# PRO_controller.net
KiCad netlist of a schematic drawn in EAGLE
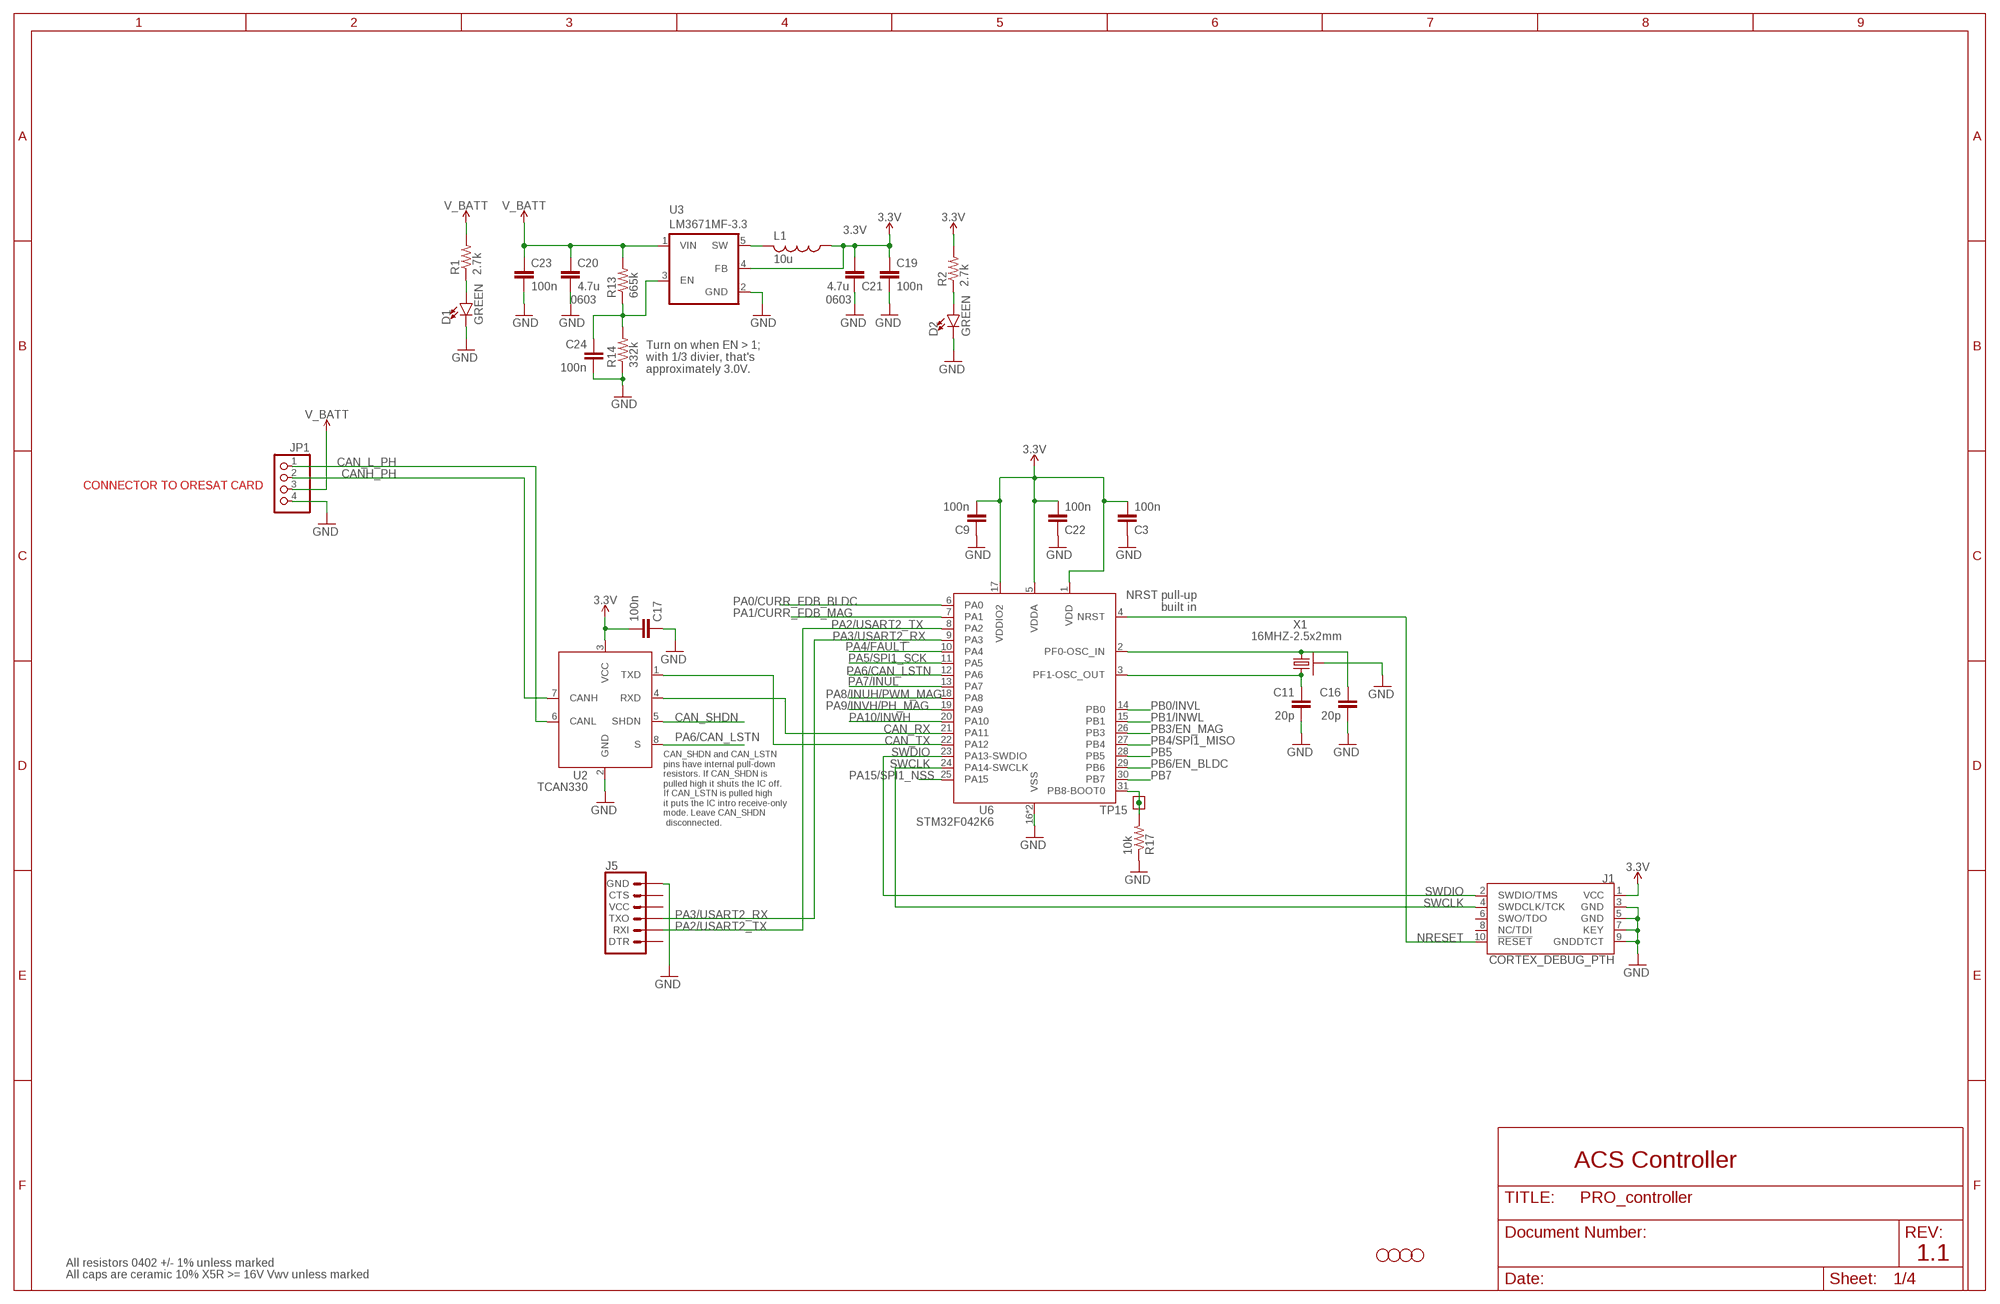
[diagram p0: schematic, sheet 1]
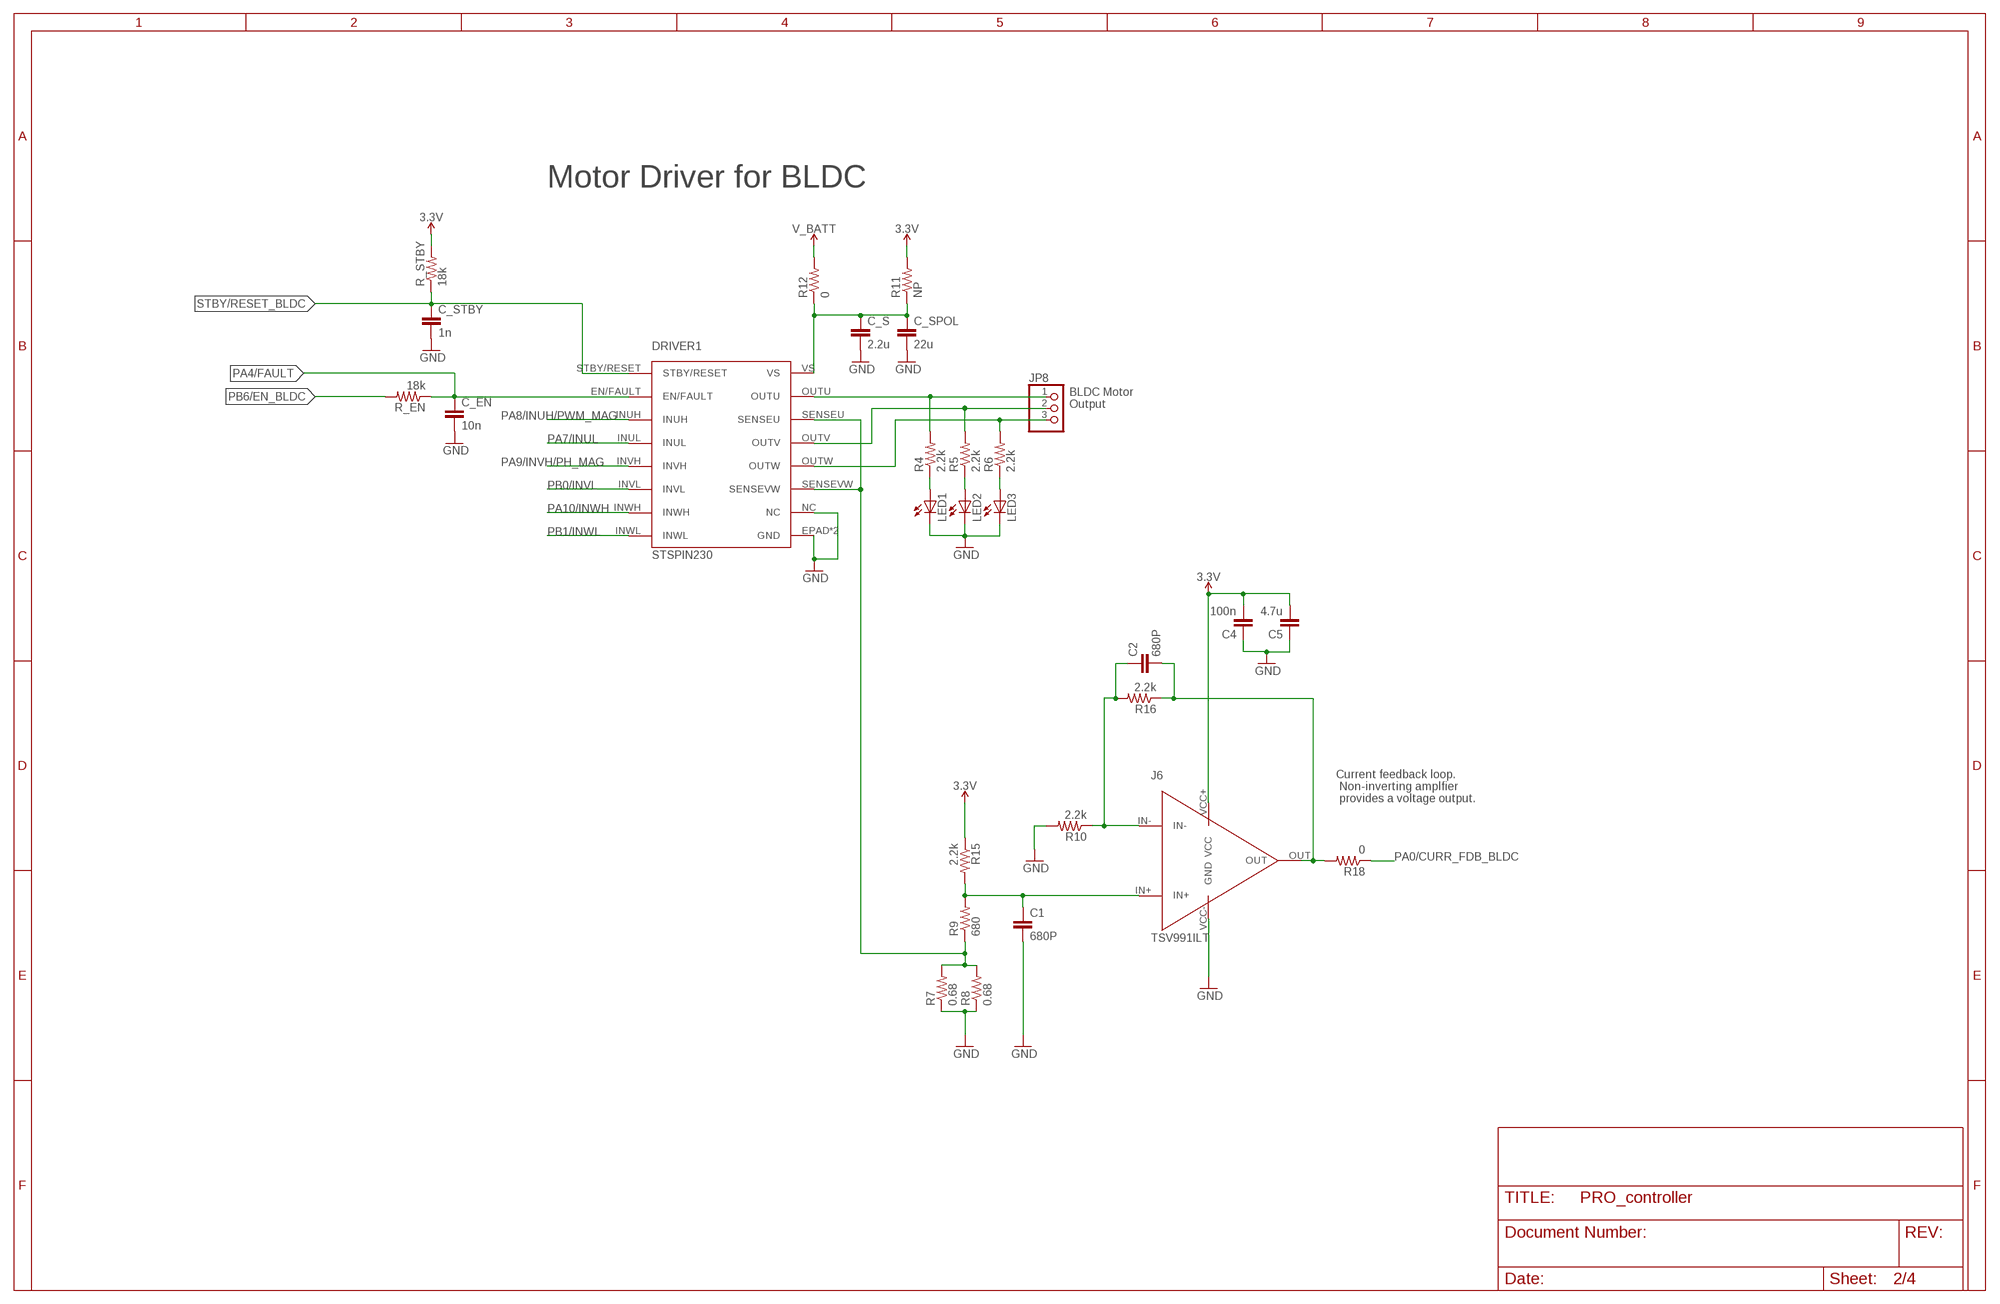
[diagram p1: schematic, sheet 2]
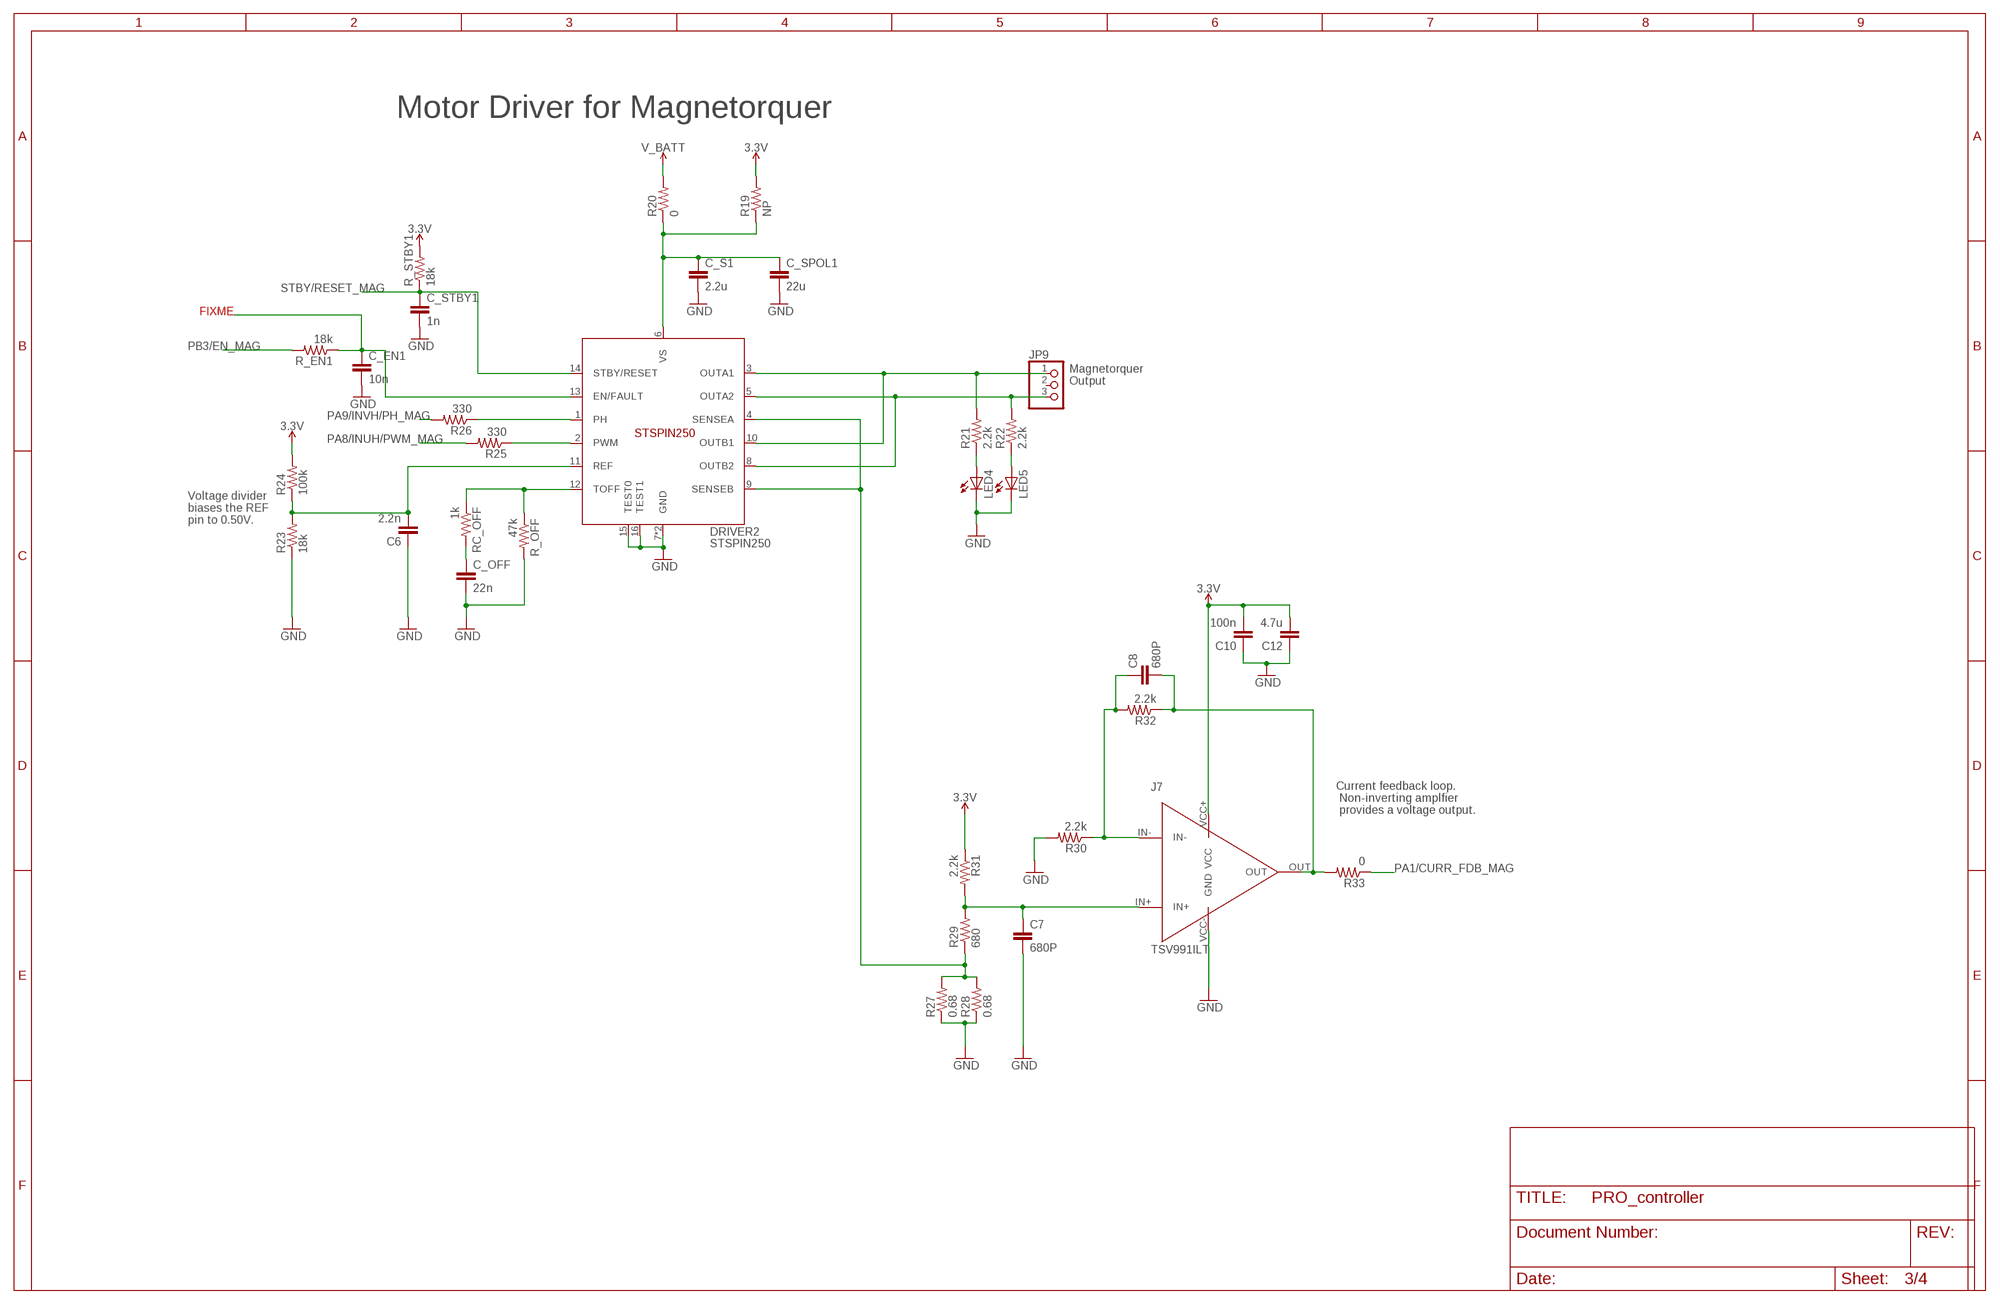
[diagram p2: schematic, sheet 3]
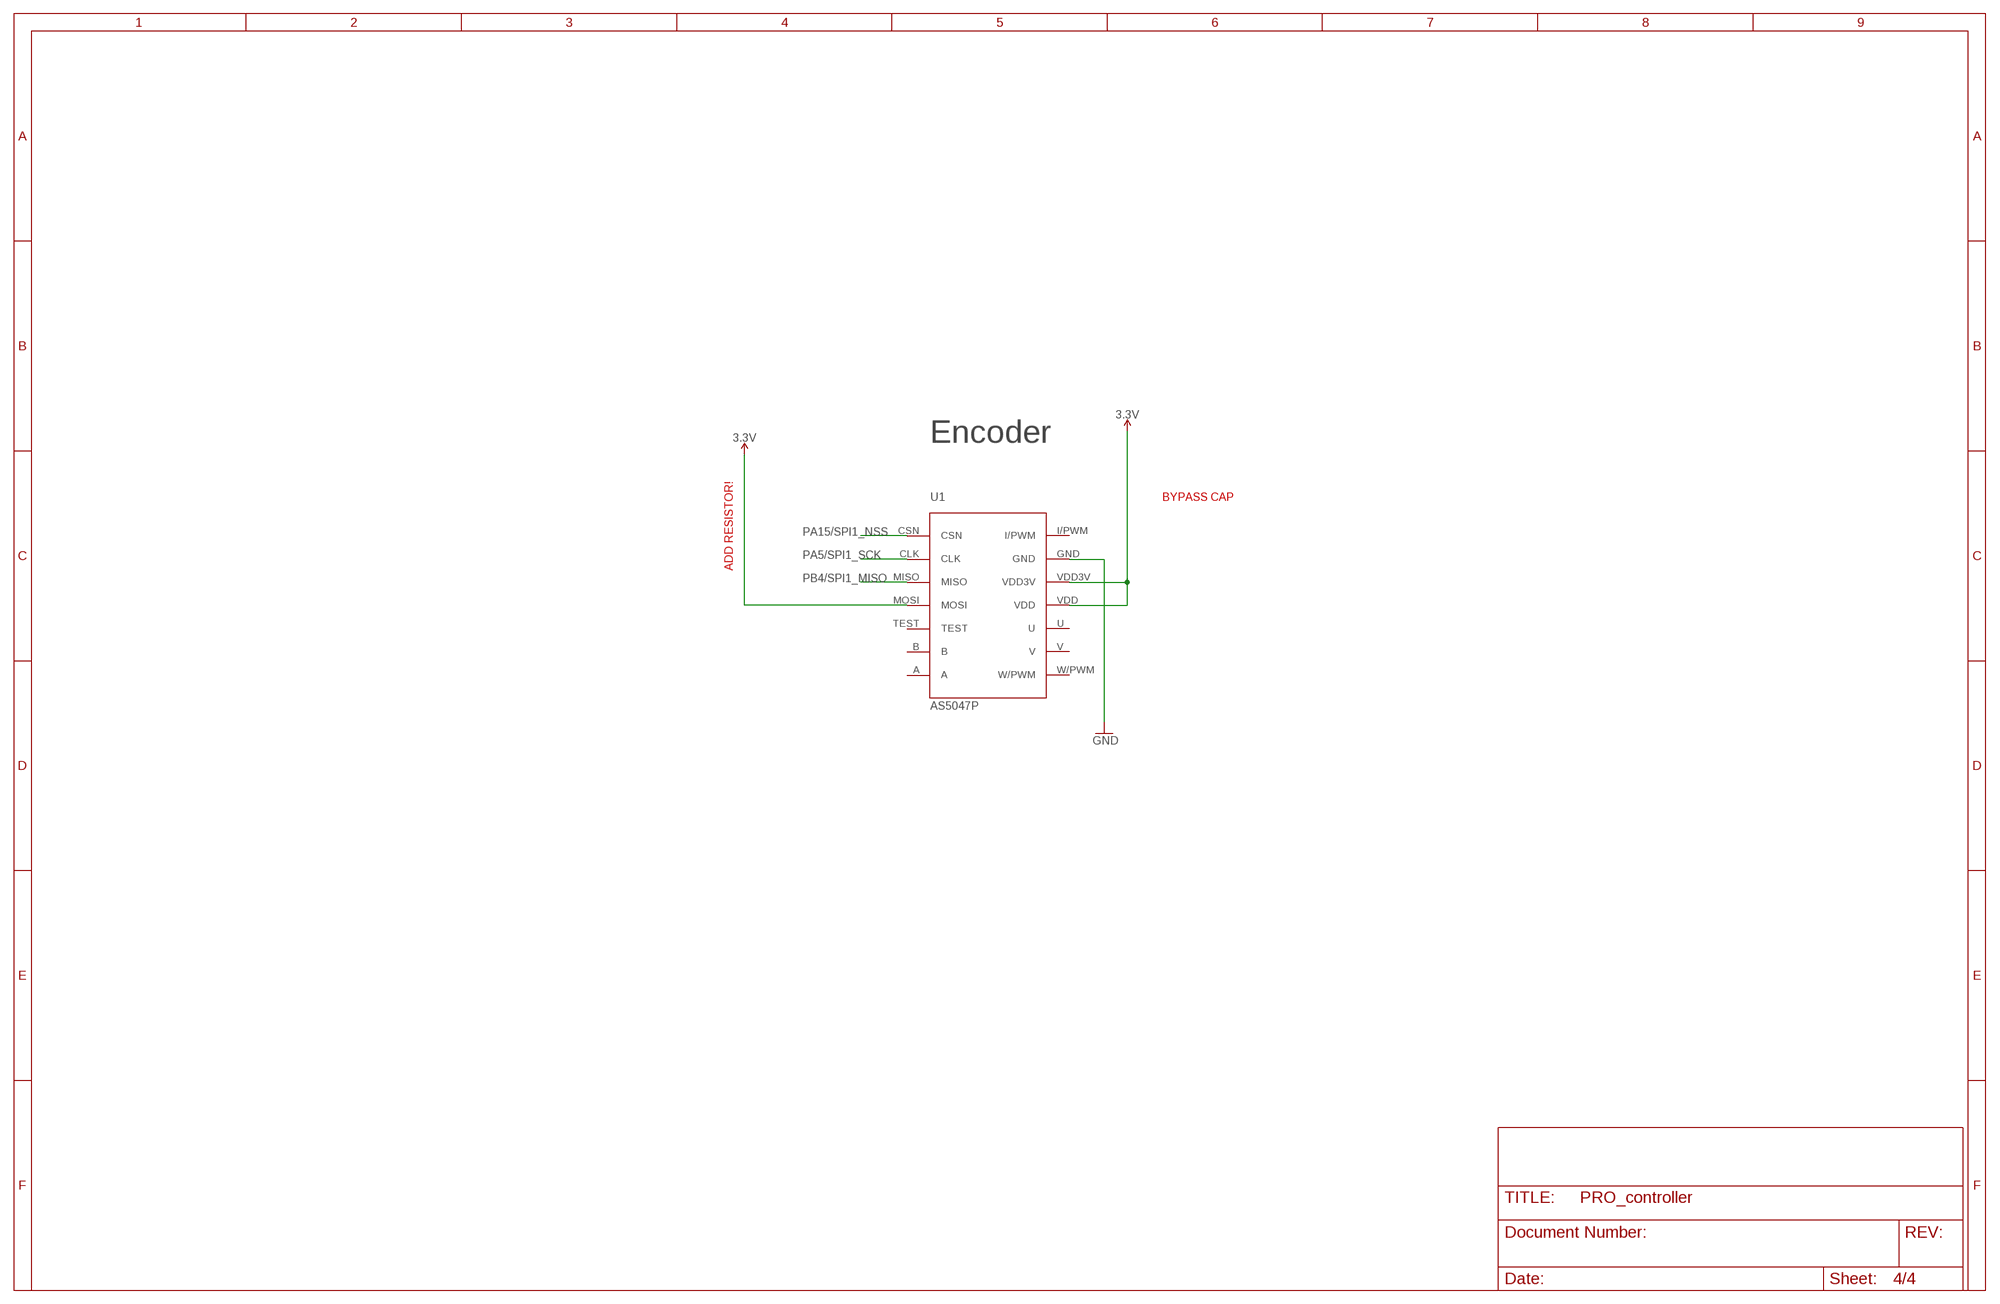
[diagram p3: schematic, sheet 4]

(export (version "E")
  (design (tool "Eeschema 10.0.6"))
  (components
    (comp (ref "U1")
      (value "AS5047P")
      (footprint "eagle-import:TSSOP14")
      (libsource (lib "eagle-import") (part "AS5047P"))
    )
    (comp (ref "C3")
      (value "100n")
      (footprint "eagle-import:.0402-B-NOSILK")
      (fields (field (name "MFR") "Samsung") (field (name "MPN") "CL05B104KO5NNNC"))
      (libsource (lib "eagle-import") (part "C-EU0402-B-NOSILK"))
    )
    (comp (ref "C9")
      (value "100n")
      (footprint "eagle-import:.0402-B-NOSILK")
      (fields (field (name "MFR") "Samsung") (field (name "MPN") "CL05B104KO5NNNC"))
      (libsource (lib "eagle-import") (part "C-EU0402-B-NOSILK"))
    )
    (comp (ref "C11")
      (value "20p")
      (footprint "eagle-import:.0402-B-NOSILK")
      (fields (field (name "MFR") "Samsung") (field (name "MPN") "CL05C200JB51PNC"))
      (libsource (lib "eagle-import") (part "C-EU0402-B-NOSILK"))
    )
    (comp (ref "C16")
      (value "20p")
      (footprint "eagle-import:.0402-B-NOSILK")
      (fields (field (name "MFR") "Samsung") (field (name "MPN") "CL05C200JB51PNC"))
      (libsource (lib "eagle-import") (part "C-EU0402-B-NOSILK"))
    )
    (comp (ref "C17")
      (value "100n")
      (footprint "eagle-import:.0402-B-NOSILK")
      (fields (field (name "MFR") "Samsung") (field (name "MPN") "CL05B104KO5NNNC"))
      (libsource (lib "eagle-import") (part "C-EU0402-B-NOSILK"))
    )
    (comp (ref "C19")
      (value "100n")
      (footprint "eagle-import:.0402-B-NOSILK")
      (fields (field (name "MFR") "Samsung") (field (name "MPN") "CL05B104KO5NNNC"))
      (libsource (lib "eagle-import") (part "C-EU0402-B-NOSILK"))
    )
    (comp (ref "C20")
      (value "4.7u")
      (footprint "eagle-import:C0603")
      (fields (field (name "MFR") "Samsung") (field (name "MPN") "CL05B104KO5NNNC"))
      (libsource (lib "eagle-import") (part "C-EUC0603"))
    )
    (comp (ref "C21")
      (value "4.7u")
      (footprint "eagle-import:C0603")
      (fields (field (name "MFR") "Samsung") (field (name "MPN") "CL05B104KO5NNNC"))
      (libsource (lib "eagle-import") (part "C-EUC0603"))
    )
    (comp (ref "C22")
      (value "100n")
      (footprint "eagle-import:.0402-B-NOSILK")
      (fields (field (name "MFR") "Samsung") (field (name "MPN") "CL05B104KO5NNNC"))
      (libsource (lib "eagle-import") (part "C-EU0402-B-NOSILK"))
    )
    (comp (ref "C23")
      (value "100n")
      (footprint "eagle-import:.0402-B-NOSILK")
      (fields (field (name "MFR") "Samsung") (field (name "MPN") "CL05B104KO5NNNC"))
      (libsource (lib "eagle-import") (part "C-EU0402-B-NOSILK"))
    )
    (comp (ref "C24")
      (value "100n")
      (footprint "eagle-import:.0402-B-NOSILK")
      (fields (field (name "MFR") "Samsung") (field (name "MPN") "CL05B104KO5NNNC"))
      (libsource (lib "eagle-import") (part "C-EU0402-B-NOSILK"))
    )
    (comp (ref "D1")
      (value "GREEN")
      (footprint "eagle-import:LED-0603")
      (libsource (lib "eagle-import") (part "LED-GREEN0603"))
    )
    (comp (ref "D2")
      (value "GREEN")
      (footprint "eagle-import:LED-0603")
      (libsource (lib "eagle-import") (part "LED-GREEN0603"))
    )
    (comp (ref "H1")
      (value "STAND-OFFTIGHT")
      (footprint "eagle-import:STAND-OFF-TIGHT")
      (libsource (lib "eagle-import") (part "STAND-OFFTIGHT"))
    )
    (comp (ref "H2")
      (value "STAND-OFFTIGHT")
      (footprint "eagle-import:STAND-OFF-TIGHT")
      (libsource (lib "eagle-import") (part "STAND-OFFTIGHT"))
    )
    (comp (ref "H3")
      (value "STAND-OFFTIGHT")
      (footprint "eagle-import:STAND-OFF-TIGHT")
      (libsource (lib "eagle-import") (part "STAND-OFFTIGHT"))
    )
    (comp (ref "H4")
      (value "STAND-OFFTIGHT")
      (footprint "eagle-import:STAND-OFF-TIGHT")
      (libsource (lib "eagle-import") (part "STAND-OFFTIGHT"))
    )
    (comp (ref "J1")
      (value "CORTEX_DEBUG_PTH")
      (footprint "eagle-import:2X5-PTH-1.27MM")
      (libsource (lib "eagle-import") (part "CORTEX_DEBUG_PTH"))
    )
    (comp (ref "J5")
      (value "6_PIN_SERIAL_TARGETSILK")
      (footprint "eagle-import:6_PIN_SERIAL_TARGET_SIDE_W_SILK")
      (libsource (lib "eagle-import") (part "6_PIN_SERIAL_TARGETSILK"))
    )
    (comp (ref "JP1")
      (value "PINHD-1X4")
      (footprint "eagle-import:1X04")
      (libsource (lib "eagle-import") (part "PINHD-1X4"))
    )
    (comp (ref "L1")
      (value "10u")
      (footprint "eagle-import:L2012C")
      (fields (field (name "MFR") "Taiyo Yuden") (field (name "MPN") "CB2012T100KR"))
      (libsource (lib "eagle-import") (part "L-USL2012C"))
    )
    (comp (ref "R1")
      (value "2.7k")
      (footprint "eagle-import:.0402-B-NOSILK")
      (fields (field (name "MFR") "Samsung") (field (name "MPN") "RC1005F6653CS"))
      (libsource (lib "eagle-import") (part "R-US_0402-B-NOSILK"))
    )
    (comp (ref "R2")
      (value "2.7k")
      (footprint "eagle-import:.0402-B-NOSILK")
      (fields (field (name "MFR") "Samsung") (field (name "MPN") "RC1005F6653CS"))
      (libsource (lib "eagle-import") (part "R-US_0402-B-NOSILK"))
    )
    (comp (ref "R13")
      (value "665k")
      (footprint "eagle-import:.0402-B-NOSILK")
      (fields (field (name "MFR") "Samsung") (field (name "MPN") "RC1005F6653CS"))
      (libsource (lib "eagle-import") (part "R-US_0402-B-NOSILK"))
    )
    (comp (ref "R14")
      (value "332k")
      (footprint "eagle-import:.0402-B-NOSILK")
      (fields (field (name "MFR") "Samsung") (field (name "MPN") "RC1005F3323CS"))
      (libsource (lib "eagle-import") (part "R-US_0402-B-NOSILK"))
    )
    (comp (ref "R17")
      (value "10k")
      (footprint "eagle-import:.0402-B-NOSILK")
      (fields (field (name "MFR") "Samsung") (field (name "MPN") "RC1005F6653CS"))
      (libsource (lib "eagle-import") (part "R-US_0402-B-NOSILK"))
    )
    (comp (ref "TP15")
      (value "TEST-POINT")
      (footprint "eagle-import:2MM-TEST-POINT")
      (libsource (lib "eagle-import") (part "TEST-POINT"))
    )
    (comp (ref "U2")
      (value "TCAN330")
      (footprint "eagle-import:SOT23-8_TI-DCN")
      (fields (field (name "MFR") "Texas Instruments") (field (name "MPN") "TCAN330GDCNT"))
      (libsource (lib "eagle-import") (part "TCAN330"))
    )
    (comp (ref "U3")
      (value "LM3671MF-3.3")
      (footprint "eagle-import:SOT23-5")
      (fields (field (name "MFR") "TI") (field (name "MPN") "LM3671MF-3.3/NOPB"))
      (libsource (lib "eagle-import") (part "LM3761"))
    )
    (comp (ref "U6")
      (value "STM32F042K6")
      (footprint "eagle-import:QFP32-7X7")
      (fields (field (name "MFR") "STMicroelectronics") (field (name "MPN") "STM32F042K6T7"))
      (libsource (lib "eagle-import") (part "STM32F042K6"))
    )
    (comp (ref "X1")
      (value "16MHZ-2.5x2mm")
      (footprint "eagle-import:CRYSTAL_2.5X2")
      (fields (field (name "MFR") "ECS Inc.") (field (name "MPN") "ECS-160-10-36Q-ES-TR"))
      (libsource (lib "eagle-import") (part "CRYSTAL-WITH-GND"))
    )
    (comp (ref "C6")
      (value "2.2n")
      (footprint "eagle-import:C0402")
      (libsource (lib "eagle-import") (part "rcl_334_C-EUC0402"))
    )
    (comp (ref "C7")
      (value "680P")
      (footprint "eagle-import:C0402")
      (libsource (lib "eagle-import") (part "rcl_334_C-EUC0402"))
    )
    (comp (ref "C8")
      (value "680P")
      (footprint "eagle-import:C0402")
      (libsource (lib "eagle-import") (part "rcl_334_C-EUC0402"))
    )
    (comp (ref "C10")
      (value "100n")
      (footprint "eagle-import:C0402")
      (libsource (lib "eagle-import") (part "rcl_334_C-EUC0402"))
    )
    (comp (ref "C12")
      (value "4.7u")
      (footprint "eagle-import:C0402")
      (libsource (lib "eagle-import") (part "rcl_334_C-EUC0402"))
    )
    (comp (ref "C_EN1")
      (value "10n")
      (footprint "eagle-import:C0402")
      (libsource (lib "eagle-import") (part "rcl_334_C-EUC0402"))
    )
    (comp (ref "C_OFF")
      (value "22n")
      (footprint "eagle-import:C0402")
      (libsource (lib "eagle-import") (part "rcl_334_C-EUC0402"))
    )
    (comp (ref "C_S1")
      (value "2.2u")
      (footprint "eagle-import:C0402")
      (libsource (lib "eagle-import") (part "rcl_334_C-EUC0402"))
    )
    (comp (ref "C_SPOL1")
      (value "22u")
      (footprint "eagle-import:C0402")
      (libsource (lib "eagle-import") (part "rcl_334_C-EUC0402"))
    )
    (comp (ref "C_STBY1")
      (value "1n")
      (footprint "eagle-import:C0402")
      (libsource (lib "eagle-import") (part "rcl_334_C-EUC0402"))
    )
    (comp (ref "DRIVER2")
      (value "STSPIN250")
      (footprint "eagle-import:VFQFPN")
      (libsource (lib "eagle-import") (part "STSPIN250"))
    )
    (comp (ref "J7")
      (value "TSV991ILT")
      (footprint "eagle-import:SOT23-5")
      (libsource (lib "eagle-import") (part "TSV991ILT"))
    )
    (comp (ref "JP9")
      (value "PINHD-1X3")
      (footprint "eagle-import:1X03")
      (libsource (lib "eagle-import") (part "PINHD-1X3"))
    )
    (comp (ref "LED4")
      (value "LEDCHIP-LED0603")
      (footprint "eagle-import:CHIP-LED0603")
      (libsource (lib "eagle-import") (part "LEDCHIP-LED0603"))
    )
    (comp (ref "LED5")
      (value "LEDCHIP-LED0603")
      (footprint "eagle-import:CHIP-LED0603")
      (libsource (lib "eagle-import") (part "LEDCHIP-LED0603"))
    )
    (comp (ref "R19")
      (value "NP")
      (footprint "eagle-import:R0402")
      (libsource (lib "eagle-import") (part "R-US_R0402"))
    )
    (comp (ref "R20")
      (value "0")
      (footprint "eagle-import:R0402")
      (libsource (lib "eagle-import") (part "R-US_R0402"))
    )
    (comp (ref "R21")
      (value "2.2k")
      (footprint "eagle-import:R0402")
      (libsource (lib "eagle-import") (part "R-US_R0402"))
    )
    (comp (ref "R22")
      (value "2.2k")
      (footprint "eagle-import:R0402")
      (libsource (lib "eagle-import") (part "R-US_R0402"))
    )
    (comp (ref "R23")
      (value "18k")
      (footprint "eagle-import:R0402")
      (libsource (lib "eagle-import") (part "R-US_R0402"))
    )
    (comp (ref "R24")
      (value "100k")
      (footprint "eagle-import:R0402")
      (libsource (lib "eagle-import") (part "R-US_R0402"))
    )
    (comp (ref "R25")
      (value "330")
      (footprint "eagle-import:R0402")
      (libsource (lib "eagle-import") (part "R-US_R0402"))
    )
    (comp (ref "R26")
      (value "330")
      (footprint "eagle-import:R0402")
      (libsource (lib "eagle-import") (part "R-US_R0402"))
    )
    (comp (ref "R27")
      (value "0.68")
      (footprint "eagle-import:R0402")
      (libsource (lib "eagle-import") (part "R-US_R0402"))
    )
    (comp (ref "R28")
      (value "0.68")
      (footprint "eagle-import:R0402")
      (libsource (lib "eagle-import") (part "R-US_R0402"))
    )
    (comp (ref "R29")
      (value "680")
      (footprint "eagle-import:R0402")
      (libsource (lib "eagle-import") (part "R-US_R0402"))
    )
    (comp (ref "R30")
      (value "2.2k")
      (footprint "eagle-import:R0402")
      (libsource (lib "eagle-import") (part "R-US_R0402"))
    )
    (comp (ref "R31")
      (value "2.2k")
      (footprint "eagle-import:R0402")
      (libsource (lib "eagle-import") (part "R-US_R0402"))
    )
    (comp (ref "R32")
      (value "2.2k")
      (footprint "eagle-import:R0402")
      (libsource (lib "eagle-import") (part "R-US_R0402"))
    )
    (comp (ref "R33")
      (value "0")
      (footprint "eagle-import:R0402")
      (libsource (lib "eagle-import") (part "R-US_R0402"))
    )
    (comp (ref "RC_OFF")
      (value "1k")
      (footprint "eagle-import:R0402")
      (libsource (lib "eagle-import") (part "R-US_R0402"))
    )
    (comp (ref "R_EN1")
      (value "18k")
      (footprint "eagle-import:R0402")
      (libsource (lib "eagle-import") (part "R-US_R0402"))
    )
    (comp (ref "R_OFF")
      (value "47k")
      (footprint "eagle-import:R0402")
      (libsource (lib "eagle-import") (part "R-US_R0402"))
    )
    (comp (ref "R_STBY1")
      (value "18k")
      (footprint "eagle-import:R0402")
      (libsource (lib "eagle-import") (part "R-US_R0402"))
    )
    (comp (ref "C1")
      (value "680P")
      (footprint "eagle-import:C0402")
      (libsource (lib "eagle-import") (part "rcl_334_C-EUC0402"))
    )
    (comp (ref "C2")
      (value "680P")
      (footprint "eagle-import:C0402")
      (libsource (lib "eagle-import") (part "rcl_334_C-EUC0402"))
    )
    (comp (ref "C4")
      (value "100n")
      (footprint "eagle-import:C0402")
      (libsource (lib "eagle-import") (part "rcl_334_C-EUC0402"))
    )
    (comp (ref "C5")
      (value "4.7u")
      (footprint "eagle-import:C0402")
      (libsource (lib "eagle-import") (part "rcl_334_C-EUC0402"))
    )
    (comp (ref "C_EN")
      (value "10n")
      (footprint "eagle-import:C0402")
      (libsource (lib "eagle-import") (part "rcl_334_C-EUC0402"))
    )
    (comp (ref "C_S")
      (value "2.2u")
      (footprint "eagle-import:C0402")
      (libsource (lib "eagle-import") (part "rcl_334_C-EUC0402"))
    )
    (comp (ref "C_SPOL")
      (value "22u")
      (footprint "eagle-import:C0402")
      (libsource (lib "eagle-import") (part "rcl_334_C-EUC0402"))
    )
    (comp (ref "C_STBY")
      (value "1n")
      (footprint "eagle-import:C0402")
      (libsource (lib "eagle-import") (part "rcl_334_C-EUC0402"))
    )
    (comp (ref "DRIVER1")
      (value "STSPIN230")
      (footprint "eagle-import:STSPIN230")
      (libsource (lib "eagle-import") (part "STSPIN230"))
    )
    (comp (ref "J6")
      (value "TSV991ILT")
      (footprint "eagle-import:SOT23-5")
      (libsource (lib "eagle-import") (part "TSV991ILT"))
    )
    (comp (ref "JP8")
      (value "PINHD-1X3")
      (footprint "eagle-import:1X03")
      (libsource (lib "eagle-import") (part "PINHD-1X3"))
    )
    (comp (ref "LED1")
      (value "LEDCHIP-LED0603")
      (footprint "eagle-import:CHIP-LED0603")
      (libsource (lib "eagle-import") (part "LEDCHIP-LED0603"))
    )
    (comp (ref "LED2")
      (value "LEDCHIP-LED0603")
      (footprint "eagle-import:CHIP-LED0603")
      (libsource (lib "eagle-import") (part "LEDCHIP-LED0603"))
    )
    (comp (ref "LED3")
      (value "LEDCHIP-LED0603")
      (footprint "eagle-import:CHIP-LED0603")
      (libsource (lib "eagle-import") (part "LEDCHIP-LED0603"))
    )
    (comp (ref "R4")
      (value "2.2k")
      (footprint "eagle-import:R0402")
      (libsource (lib "eagle-import") (part "R-US_R0402"))
    )
    (comp (ref "R5")
      (value "2.2k")
      (footprint "eagle-import:R0402")
      (libsource (lib "eagle-import") (part "R-US_R0402"))
    )
    (comp (ref "R6")
      (value "2.2k")
      (footprint "eagle-import:R0402")
      (libsource (lib "eagle-import") (part "R-US_R0402"))
    )
    (comp (ref "R7")
      (value "0.68")
      (footprint "eagle-import:R0402")
      (libsource (lib "eagle-import") (part "R-US_R0402"))
    )
    (comp (ref "R8")
      (value "0.68")
      (footprint "eagle-import:R0402")
      (libsource (lib "eagle-import") (part "R-US_R0402"))
    )
    (comp (ref "R9")
      (value "680")
      (footprint "eagle-import:R0402")
      (libsource (lib "eagle-import") (part "R-US_R0402"))
    )
    (comp (ref "R10")
      (value "2.2k")
      (footprint "eagle-import:R0402")
      (libsource (lib "eagle-import") (part "R-US_R0402"))
    )
    (comp (ref "R11")
      (value "NP")
      (footprint "eagle-import:R0402")
      (libsource (lib "eagle-import") (part "R-US_R0402"))
    )
    (comp (ref "R12")
      (value "0")
      (footprint "eagle-import:R0402")
      (libsource (lib "eagle-import") (part "R-US_R0402"))
    )
    (comp (ref "R15")
      (value "2.2k")
      (footprint "eagle-import:R0402")
      (libsource (lib "eagle-import") (part "R-US_R0402"))
    )
    (comp (ref "R16")
      (value "2.2k")
      (footprint "eagle-import:R0402")
      (libsource (lib "eagle-import") (part "R-US_R0402"))
    )
    (comp (ref "R18")
      (value "0")
      (footprint "eagle-import:R0402")
      (libsource (lib "eagle-import") (part "R-US_R0402"))
    )
    (comp (ref "R_EN")
      (value "18k")
      (footprint "eagle-import:R0402")
      (libsource (lib "eagle-import") (part "R-US_R0402"))
    )
    (comp (ref "R_STBY")
      (value "18k")
      (footprint "eagle-import:R0402")
      (libsource (lib "eagle-import") (part "R-US_R0402"))
    )
  )
  (nets
    (net (code "1") (name "3.3V") (class "Default")
      (node (ref "C10") (pin "2") (pinfunction "2_2") (pintype "passive"))
      (node (ref "C12") (pin "2") (pinfunction "2_2") (pintype "passive"))
      (node (ref "C17") (pin "2") (pinfunction "2_2") (pintype "passive"))
      (node (ref "C19") (pin "1") (pinfunction "1_1") (pintype "passive"))
      (node (ref "C21") (pin "1") (pinfunction "1_1") (pintype "passive"))
      (node (ref "C22") (pin "2") (pinfunction "2_2") (pintype "passive"))
      (node (ref "C3") (pin "2") (pinfunction "2_2") (pintype "passive"))
      (node (ref "C4") (pin "2") (pinfunction "2_2") (pintype "passive"))
      (node (ref "C5") (pin "2") (pinfunction "2_2") (pintype "passive"))
      (node (ref "C9") (pin "2") (pinfunction "2_2") (pintype "passive"))
      (node (ref "J1") (pin "1") (pinfunction "VCC_1") (pintype "bidirectional"))
      (node (ref "J6") (pin "VCC+") (pinfunction "VCC_VCC+") (pintype "bidirectional"))
      (node (ref "J7") (pin "VCC+") (pinfunction "VCC_VCC+") (pintype "bidirectional"))
      (node (ref "L1") (pin "1") (pinfunction "1_1") (pintype "passive"))
      (node (ref "R11") (pin "2") (pinfunction "2_2") (pintype "passive"))
      (node (ref "R15") (pin "1") (pinfunction "1_1") (pintype "passive"))
      (node (ref "R19") (pin "2") (pinfunction "2_2") (pintype "passive"))
      (node (ref "R2") (pin "2") (pinfunction "2_2") (pintype "passive"))
      (node (ref "R24") (pin "2") (pinfunction "2_2") (pintype "passive"))
      (node (ref "R31") (pin "1") (pinfunction "1_1") (pintype "passive"))
      (node (ref "R_STBY") (pin "2") (pinfunction "2_2") (pintype "passive"))
      (node (ref "R_STBY1") (pin "2") (pinfunction "2_2") (pintype "passive"))
      (node (ref "U1") (pin "MOSI") (pinfunction "MOSI_MOSI") (pintype "bidirectional"))
      (node (ref "U1") (pin "VDD") (pinfunction "VDD_VDD") (pintype "bidirectional"))
      (node (ref "U1") (pin "VDD3V") (pinfunction "VDD3V_VDD3V") (pintype "bidirectional"))
      (node (ref "U2") (pin "3") (pinfunction "VCC_3") (pintype "power_in"))
      (node (ref "U3") (pin "4") (pinfunction "FB_4") (pintype "input"))
      (node (ref "U6") (pin "1") (pinfunction "VDD_1") (pintype "power_in"))
      (node (ref "U6") (pin "17") (pinfunction "VDDIO2_17") (pintype "power_in"))
      (node (ref "U6") (pin "5") (pinfunction "VDDA_5") (pintype "power_in"))
    )
    (net (code "2") (name "CANH_PH") (class "Default")
      (node (ref "JP1") (pin "2") (pinfunction "2_2") (pintype "passive"))
      (node (ref "U2") (pin "7") (pinfunction "CANH_7") (pintype "bidirectional"))
    )
    (net (code "3") (name "CAN_L_PH") (class "Default")
      (node (ref "JP1") (pin "1") (pinfunction "1_1") (pintype "passive"))
      (node (ref "U2") (pin "6") (pinfunction "CANL_6") (pintype "bidirectional"))
    )
    (net (code "4") (name "CAN_RX") (class "Default")
      (node (ref "U2") (pin "4") (pinfunction "RXD_4") (pintype "output"))
      (node (ref "U6") (pin "21") (pinfunction "PA11_21") (pintype "bidirectional"))
    )
    (net (code "5") (name "CAN_SHDN") (class "Default")
      (node (ref "U2") (pin "5") (pinfunction "SHDN_5") (pintype "input"))
    )
    (net (code "6") (name "CAN_TX") (class "Default")
      (node (ref "U2") (pin "1") (pinfunction "TXD_1") (pintype "input"))
      (node (ref "U6") (pin "22") (pinfunction "PA12_22") (pintype "bidirectional"))
    )
    (net (code "7") (name "GND") (class "Default")
      (node (ref "C1") (pin "2") (pinfunction "2_2") (pintype "passive"))
      (node (ref "C10") (pin "1") (pinfunction "1_1") (pintype "passive"))
      (node (ref "C11") (pin "2") (pinfunction "2_2") (pintype "passive"))
      (node (ref "C12") (pin "1") (pinfunction "1_1") (pintype "passive"))
      (node (ref "C16") (pin "2") (pinfunction "2_2") (pintype "passive"))
      (node (ref "C17") (pin "1") (pinfunction "1_1") (pintype "passive"))
      (node (ref "C19") (pin "2") (pinfunction "2_2") (pintype "passive"))
      (node (ref "C20") (pin "2") (pinfunction "2_2") (pintype "passive"))
      (node (ref "C21") (pin "2") (pinfunction "2_2") (pintype "passive"))
      (node (ref "C22") (pin "1") (pinfunction "1_1") (pintype "passive"))
      (node (ref "C23") (pin "2") (pinfunction "2_2") (pintype "passive"))
      (node (ref "C24") (pin "2") (pinfunction "2_2") (pintype "passive"))
      (node (ref "C3") (pin "1") (pinfunction "1_1") (pintype "passive"))
      (node (ref "C4") (pin "1") (pinfunction "1_1") (pintype "passive"))
      (node (ref "C5") (pin "1") (pinfunction "1_1") (pintype "passive"))
      (node (ref "C6") (pin "1") (pinfunction "1_1") (pintype "passive"))
      (node (ref "C7") (pin "2") (pinfunction "2_2") (pintype "passive"))
      (node (ref "C9") (pin "1") (pinfunction "1_1") (pintype "passive"))
      (node (ref "C_EN") (pin "2") (pinfunction "2_2") (pintype "passive"))
      (node (ref "C_EN1") (pin "2") (pinfunction "2_2") (pintype "passive"))
      (node (ref "C_OFF") (pin "2") (pinfunction "2_2") (pintype "passive"))
      (node (ref "C_S") (pin "2") (pinfunction "2_2") (pintype "passive"))
      (node (ref "C_S1") (pin "2") (pinfunction "2_2") (pintype "passive"))
      (node (ref "C_SPOL") (pin "2") (pinfunction "2_2") (pintype "passive"))
      (node (ref "C_SPOL1") (pin "2") (pinfunction "2_2") (pintype "passive"))
      (node (ref "C_STBY") (pin "2") (pinfunction "2_2") (pintype "passive"))
      (node (ref "C_STBY1") (pin "2") (pinfunction "2_2") (pintype "passive"))
      (node (ref "D1") (pin "C") (pinfunction "C_C") (pintype "passive"))
      (node (ref "D2") (pin "C") (pinfunction "C_C") (pintype "passive"))
      (node (ref "DRIVER1") (pin "EPAD") (pinfunction "GND_EPAD") (pintype "bidirectional"))
      (node (ref "DRIVER1") (pin "GND") (pinfunction "GND_GND") (pintype "bidirectional"))
      (node (ref "DRIVER1") (pin "NC") (pinfunction "NC_NC") (pintype "bidirectional"))
      (node (ref "DRIVER2") (pin "15") (pinfunction "TEST0_15") (pintype "bidirectional"))
      (node (ref "DRIVER2") (pin "16") (pinfunction "TEST1_16") (pintype "bidirectional"))
      (node (ref "DRIVER2") (pin "7") (pinfunction "GND_7") (pintype "power_in"))
      (node (ref "DRIVER2") (pin "EPAD") (pinfunction "GND_EPAD") (pintype "power_in"))
      (node (ref "J1") (pin "3") (pinfunction "GND_3") (pintype "bidirectional"))
      (node (ref "J1") (pin "5") (pinfunction "GND_5") (pintype "bidirectional"))
      (node (ref "J1") (pin "7") (pinfunction "KEY_7") (pintype "bidirectional"))
      (node (ref "J1") (pin "9") (pinfunction "GNDDTCT_9") (pintype "bidirectional"))
      (node (ref "J5") (pin "P$6") (pinfunction "GND_P$6") (pintype "passive"))
      (node (ref "J6") (pin "VCC-") (pinfunction "GND_VCC-") (pintype "bidirectional"))
      (node (ref "J7") (pin "VCC-") (pinfunction "GND_VCC-") (pintype "bidirectional"))
      (node (ref "JP1") (pin "4") (pinfunction "4_4") (pintype "passive"))
      (node (ref "LED1") (pin "C") (pinfunction "C_C") (pintype "passive"))
      (node (ref "LED2") (pin "C") (pinfunction "C_C") (pintype "passive"))
      (node (ref "LED3") (pin "C") (pinfunction "C_C") (pintype "passive"))
      (node (ref "LED4") (pin "C") (pinfunction "C_C") (pintype "passive"))
      (node (ref "LED5") (pin "C") (pinfunction "C_C") (pintype "passive"))
      (node (ref "R10") (pin "2") (pinfunction "2_2") (pintype "passive"))
      (node (ref "R14") (pin "1") (pinfunction "1_1") (pintype "passive"))
      (node (ref "R17") (pin "1") (pinfunction "1_1") (pintype "passive"))
      (node (ref "R23") (pin "1") (pinfunction "1_1") (pintype "passive"))
      (node (ref "R27") (pin "1") (pinfunction "1_1") (pintype "passive"))
      (node (ref "R28") (pin "1") (pinfunction "1_1") (pintype "passive"))
      (node (ref "R30") (pin "2") (pinfunction "2_2") (pintype "passive"))
      (node (ref "R7") (pin "1") (pinfunction "1_1") (pintype "passive"))
      (node (ref "R8") (pin "1") (pinfunction "1_1") (pintype "passive"))
      (node (ref "R_OFF") (pin "2") (pinfunction "2_2") (pintype "passive"))
      (node (ref "U1") (pin "GND") (pinfunction "GND_GND") (pintype "bidirectional"))
      (node (ref "U2") (pin "2") (pinfunction "GND_2") (pintype "power_in"))
      (node (ref "U3") (pin "2") (pinfunction "GND_2") (pintype "bidirectional"))
      (node (ref "U6") (pin "16") (pinfunction "VSS_16") (pintype "power_in"))
      (node (ref "U6") (pin "32") (pinfunction "VSS_32") (pintype "power_in"))
      (node (ref "X1") (pin "2") (pinfunction "SHIELD_2") (pintype "power_in"))
      (node (ref "X1") (pin "4") (pinfunction "SHIELD_4") (pintype "power_in"))
    )
    (net (code "8") (name "NRESET") (class "Default")
      (node (ref "J1") (pin "10") (pinfunction "~{RESET}_10") (pintype "bidirectional"))
      (node (ref "U6") (pin "4") (pinfunction "NRST_4") (pintype "bidirectional"))
    )
    (net (code "9") (name "Net-(C1-Pad1)") (class "Default")
      (node (ref "C1") (pin "1") (pinfunction "1_1") (pintype "passive"))
      (node (ref "J6") (pin "IN+") (pinfunction "IN+_IN+") (pintype "bidirectional"))
      (node (ref "R15") (pin "2") (pinfunction "2_2") (pintype "passive"))
      (node (ref "R9") (pin "2") (pinfunction "2_2") (pintype "passive"))
    )
    (net (code "10") (name "Net-(C2-Pad1)") (class "Default")
      (node (ref "C2") (pin "1") (pinfunction "1_1") (pintype "passive"))
      (node (ref "J6") (pin "IN-") (pinfunction "IN-_IN-") (pintype "bidirectional"))
      (node (ref "R10") (pin "1") (pinfunction "1_1") (pintype "passive"))
      (node (ref "R16") (pin "2") (pinfunction "2_2") (pintype "passive"))
    )
    (net (code "11") (name "Net-(C2-Pad2)") (class "Default")
      (node (ref "C2") (pin "2") (pinfunction "2_2") (pintype "passive"))
      (node (ref "J6") (pin "OUT") (pinfunction "OUT_OUT") (pintype "bidirectional"))
      (node (ref "R16") (pin "1") (pinfunction "1_1") (pintype "passive"))
      (node (ref "R18") (pin "2") (pinfunction "2_2") (pintype "passive"))
    )
    (net (code "12") (name "Net-(C7-Pad1)") (class "Default")
      (node (ref "C7") (pin "1") (pinfunction "1_1") (pintype "passive"))
      (node (ref "J7") (pin "IN+") (pinfunction "IN+_IN+") (pintype "bidirectional"))
      (node (ref "R29") (pin "2") (pinfunction "2_2") (pintype "passive"))
      (node (ref "R31") (pin "2") (pinfunction "2_2") (pintype "passive"))
    )
    (net (code "13") (name "Net-(C8-Pad1)") (class "Default")
      (node (ref "C8") (pin "1") (pinfunction "1_1") (pintype "passive"))
      (node (ref "J7") (pin "IN-") (pinfunction "IN-_IN-") (pintype "bidirectional"))
      (node (ref "R30") (pin "1") (pinfunction "1_1") (pintype "passive"))
      (node (ref "R32") (pin "2") (pinfunction "2_2") (pintype "passive"))
    )
    (net (code "14") (name "Net-(C8-Pad2)") (class "Default")
      (node (ref "C8") (pin "2") (pinfunction "2_2") (pintype "passive"))
      (node (ref "J7") (pin "OUT") (pinfunction "OUT_OUT") (pintype "bidirectional"))
      (node (ref "R32") (pin "1") (pinfunction "1_1") (pintype "passive"))
      (node (ref "R33") (pin "2") (pinfunction "2_2") (pintype "passive"))
    )
    (net (code "15") (name "Net-(C_OFF-Pad1)") (class "Default")
      (node (ref "C_OFF") (pin "1") (pinfunction "1_1") (pintype "passive"))
      (node (ref "RC_OFF") (pin "2") (pinfunction "2_2") (pintype "passive"))
    )
    (net (code "16") (name "Net-(C_S-Pad1)") (class "Default")
      (node (ref "C_S") (pin "1") (pinfunction "1_1") (pintype "passive"))
      (node (ref "C_SPOL") (pin "1") (pinfunction "1_1") (pintype "passive"))
      (node (ref "DRIVER1") (pin "VS") (pinfunction "VS_VS") (pintype "bidirectional"))
      (node (ref "R11") (pin "1") (pinfunction "1_1") (pintype "passive"))
      (node (ref "R12") (pin "1") (pinfunction "1_1") (pintype "passive"))
    )
    (net (code "17") (name "Net-(D1-PadA)") (class "Default")
      (node (ref "D1") (pin "A") (pinfunction "A_A") (pintype "passive"))
      (node (ref "R1") (pin "1") (pinfunction "1_1") (pintype "passive"))
    )
    (net (code "18") (name "Net-(D2-PadA)") (class "Default")
      (node (ref "D2") (pin "A") (pinfunction "A_A") (pintype "passive"))
      (node (ref "R2") (pin "1") (pinfunction "1_1") (pintype "passive"))
    )
    (net (code "19") (name "Net-(DRIVER1-PadOUTU)") (class "Default")
      (node (ref "DRIVER1") (pin "OUTU") (pinfunction "OUTU_OUTU") (pintype "bidirectional"))
      (node (ref "JP8") (pin "1") (pinfunction "1_1") (pintype "passive"))
      (node (ref "R4") (pin "2") (pinfunction "2_2") (pintype "passive"))
    )
    (net (code "20") (name "Net-(DRIVER1-PadOUTV)") (class "Default")
      (node (ref "DRIVER1") (pin "OUTV") (pinfunction "OUTV_OUTV") (pintype "bidirectional"))
      (node (ref "JP8") (pin "2") (pinfunction "2_2") (pintype "passive"))
      (node (ref "R5") (pin "2") (pinfunction "2_2") (pintype "passive"))
    )
    (net (code "21") (name "Net-(DRIVER1-PadOUTW)") (class "Default")
      (node (ref "DRIVER1") (pin "OUTW") (pinfunction "OUTW_OUTW") (pintype "bidirectional"))
      (node (ref "JP8") (pin "3") (pinfunction "3_3") (pintype "passive"))
      (node (ref "R6") (pin "2") (pinfunction "2_2") (pintype "passive"))
    )
    (net (code "22") (name "Net-(DRIVER1-PadSENSEU)") (class "Default")
      (node (ref "DRIVER1") (pin "SENSEU") (pinfunction "SENSEU_SENSEU") (pintype "bidirectional"))
      (node (ref "DRIVER1") (pin "SENSEVW") (pinfunction "SENSEVW_SENSEVW") (pintype "bidirectional"))
      (node (ref "R7") (pin "2") (pinfunction "2_2") (pintype "passive"))
      (node (ref "R8") (pin "2") (pinfunction "2_2") (pintype "passive"))
      (node (ref "R9") (pin "1") (pinfunction "1_1") (pintype "passive"))
    )
    (net (code "23") (name "Net-(DRIVER2-EN{slash}FAULT)") (class "Default")
      (node (ref "C_EN1") (pin "1") (pinfunction "1_1") (pintype "passive"))
      (node (ref "DRIVER2") (pin "13") (pinfunction "EN/FAULT_13") (pintype "bidirectional"))
      (node (ref "R_EN1") (pin "1") (pinfunction "1_1") (pintype "passive"))
    )
    (net (code "24") (name "Net-(DRIVER2-OUTA1)") (class "Default")
      (node (ref "DRIVER2") (pin "10") (pinfunction "OUTB1_10") (pintype "output"))
      (node (ref "DRIVER2") (pin "3") (pinfunction "OUTA1_3") (pintype "output"))
      (node (ref "JP9") (pin "1") (pinfunction "1_1") (pintype "passive"))
      (node (ref "R21") (pin "2") (pinfunction "2_2") (pintype "passive"))
    )
    (net (code "25") (name "Net-(DRIVER2-OUTA2)") (class "Default")
      (node (ref "DRIVER2") (pin "5") (pinfunction "OUTA2_5") (pintype "output"))
      (node (ref "DRIVER2") (pin "8") (pinfunction "OUTB2_8") (pintype "output"))
      (node (ref "JP9") (pin "3") (pinfunction "3_3") (pintype "passive"))
      (node (ref "R22") (pin "2") (pinfunction "2_2") (pintype "passive"))
    )
    (net (code "26") (name "Net-(DRIVER2-PH)") (class "Default")
      (node (ref "DRIVER2") (pin "1") (pinfunction "PH_1") (pintype "input"))
      (node (ref "R26") (pin "1") (pinfunction "1_1") (pintype "passive"))
    )
    (net (code "27") (name "Net-(DRIVER2-PWM)") (class "Default")
      (node (ref "DRIVER2") (pin "2") (pinfunction "PWM_2") (pintype "input"))
      (node (ref "R25") (pin "1") (pinfunction "1_1") (pintype "passive"))
    )
    (net (code "28") (name "Net-(DRIVER2-REF)") (class "Default")
      (node (ref "C6") (pin "2") (pinfunction "2_2") (pintype "passive"))
      (node (ref "DRIVER2") (pin "11") (pinfunction "REF_11") (pintype "passive"))
      (node (ref "R23") (pin "2") (pinfunction "2_2") (pintype "passive"))
      (node (ref "R24") (pin "1") (pinfunction "1_1") (pintype "passive"))
    )
    (net (code "29") (name "Net-(DRIVER2-SENSEA)") (class "Default")
      (node (ref "DRIVER2") (pin "4") (pinfunction "SENSEA_4") (pintype "output"))
      (node (ref "DRIVER2") (pin "9") (pinfunction "SENSEB_9") (pintype "output"))
      (node (ref "R27") (pin "2") (pinfunction "2_2") (pintype "passive"))
      (node (ref "R28") (pin "2") (pinfunction "2_2") (pintype "passive"))
      (node (ref "R29") (pin "1") (pinfunction "1_1") (pintype "passive"))
    )
    (net (code "30") (name "Net-(DRIVER2-TOFF)") (class "Default")
      (node (ref "DRIVER2") (pin "12") (pinfunction "TOFF_12") (pintype "passive"))
      (node (ref "RC_OFF") (pin "1") (pinfunction "1_1") (pintype "passive"))
      (node (ref "R_OFF") (pin "1") (pinfunction "1_1") (pintype "passive"))
    )
    (net (code "31") (name "Net-(DRIVER2-VS)") (class "Default")
      (node (ref "C_S1") (pin "1") (pinfunction "1_1") (pintype "passive"))
      (node (ref "C_SPOL1") (pin "1") (pinfunction "1_1") (pintype "passive"))
      (node (ref "DRIVER2") (pin "6") (pinfunction "VS_6") (pintype "power_in"))
      (node (ref "R19") (pin "1") (pinfunction "1_1") (pintype "passive"))
      (node (ref "R20") (pin "1") (pinfunction "1_1") (pintype "passive"))
    )
    (net (code "32") (name "Net-(LED1-PadA)") (class "Default")
      (node (ref "LED1") (pin "A") (pinfunction "A_A") (pintype "passive"))
      (node (ref "R4") (pin "1") (pinfunction "1_1") (pintype "passive"))
    )
    (net (code "33") (name "Net-(LED2-PadA)") (class "Default")
      (node (ref "LED2") (pin "A") (pinfunction "A_A") (pintype "passive"))
      (node (ref "R5") (pin "1") (pinfunction "1_1") (pintype "passive"))
    )
    (net (code "34") (name "Net-(LED3-PadA)") (class "Default")
      (node (ref "LED3") (pin "A") (pinfunction "A_A") (pintype "passive"))
      (node (ref "R6") (pin "1") (pinfunction "1_1") (pintype "passive"))
    )
    (net (code "35") (name "Net-(LED4-PadA)") (class "Default")
      (node (ref "LED4") (pin "A") (pinfunction "A_A") (pintype "passive"))
      (node (ref "R21") (pin "1") (pinfunction "1_1") (pintype "passive"))
    )
    (net (code "36") (name "Net-(LED5-PadA)") (class "Default")
      (node (ref "LED5") (pin "A") (pinfunction "A_A") (pintype "passive"))
      (node (ref "R22") (pin "1") (pinfunction "1_1") (pintype "passive"))
    )
    (net (code "37") (name "Net-(U3-EN)") (class "Default")
      (node (ref "C24") (pin "1") (pinfunction "1_1") (pintype "passive"))
      (node (ref "R13") (pin "1") (pinfunction "1_1") (pintype "passive"))
      (node (ref "R14") (pin "2") (pinfunction "2_2") (pintype "passive"))
      (node (ref "U3") (pin "3") (pinfunction "EN_3") (pintype "input"))
    )
    (net (code "38") (name "Net-(U3-SW)") (class "Default")
      (node (ref "L1") (pin "2") (pinfunction "2_2") (pintype "passive"))
      (node (ref "U3") (pin "5") (pinfunction "SW_5") (pintype "bidirectional"))
    )
    (net (code "39") (name "Net-(U6-PB8-BOOT0)") (class "Default")
      (node (ref "R17") (pin "2") (pinfunction "2_2") (pintype "passive"))
      (node (ref "TP15") (pin "1") (pinfunction "1_1") (pintype "passive"))
      (node (ref "U6") (pin "31") (pinfunction "PB8-BOOT0_31") (pintype "bidirectional"))
    )
    (net (code "40") (name "Net-(U6-PF0-OSC_IN)") (class "Default")
      (node (ref "C16") (pin "1") (pinfunction "1_1") (pintype "passive"))
      (node (ref "U6") (pin "2") (pinfunction "PF0-OSC_IN_2") (pintype "bidirectional"))
      (node (ref "X1") (pin "1") (pinfunction "1_1") (pintype "passive"))
    )
    (net (code "41") (name "Net-(U6-PF1-OSC_OUT)") (class "Default")
      (node (ref "C11") (pin "1") (pinfunction "1_1") (pintype "passive"))
      (node (ref "U6") (pin "3") (pinfunction "PF1-OSC_OUT_3") (pintype "bidirectional"))
      (node (ref "X1") (pin "3") (pinfunction "2_3") (pintype "passive"))
    )
    (net (code "42") (name "PA0{slash}CURR_FDB_BLDC") (class "Default")
      (node (ref "R18") (pin "1") (pinfunction "1_1") (pintype "passive"))
      (node (ref "U6") (pin "6") (pinfunction "PA0_6") (pintype "bidirectional"))
    )
    (net (code "43") (name "PA1{slash}CURR_FDB_MAG") (class "Default")
      (node (ref "R33") (pin "1") (pinfunction "1_1") (pintype "passive"))
      (node (ref "U6") (pin "7") (pinfunction "PA1_7") (pintype "bidirectional"))
    )
    (net (code "44") (name "PA2{slash}USART2_TX") (class "Default")
      (node (ref "J5") (pin "P$3") (pinfunction "RXI_P$3") (pintype "passive"))
      (node (ref "U6") (pin "8") (pinfunction "PA2_8") (pintype "bidirectional"))
    )
    (net (code "45") (name "PA3{slash}USART2_RX") (class "Default")
      (node (ref "J5") (pin "P$2") (pinfunction "TXO_P$2") (pintype "passive"))
      (node (ref "U6") (pin "9") (pinfunction "PA3_9") (pintype "bidirectional"))
    )
    (net (code "46") (name "PA4{slash}FAULT") (class "Default")
      (node (ref "C_EN") (pin "1") (pinfunction "1_1") (pintype "passive"))
      (node (ref "DRIVER1") (pin "EN/FAULT") (pinfunction "EN/FAULT_EN/FAULT") (pintype "bidirectional"))
      (node (ref "R_EN") (pin "1") (pinfunction "1_1") (pintype "passive"))
      (node (ref "U6") (pin "10") (pinfunction "PA4_10") (pintype "bidirectional"))
    )
    (net (code "47") (name "PA5{slash}SPI1_SCK") (class "Default")
      (node (ref "U1") (pin "CLK") (pinfunction "CLK_CLK") (pintype "bidirectional"))
      (node (ref "U6") (pin "11") (pinfunction "PA5_11") (pintype "bidirectional"))
    )
    (net (code "48") (name "PA6{slash}CAN_LSTN") (class "Default")
      (node (ref "U2") (pin "8") (pinfunction "S_8") (pintype "input"))
      (node (ref "U6") (pin "12") (pinfunction "PA6_12") (pintype "bidirectional"))
    )
    (net (code "49") (name "PA7{slash}INUL") (class "Default")
      (node (ref "DRIVER1") (pin "INUL") (pinfunction "INUL_INUL") (pintype "bidirectional"))
      (node (ref "U6") (pin "13") (pinfunction "PA7_13") (pintype "bidirectional"))
    )
    (net (code "50") (name "PA8{slash}INUH{slash}PWM_MAG") (class "Default")
      (node (ref "DRIVER1") (pin "INUH") (pinfunction "INUH_INUH") (pintype "bidirectional"))
      (node (ref "R25") (pin "2") (pinfunction "2_2") (pintype "passive"))
      (node (ref "U6") (pin "18") (pinfunction "PA8_18") (pintype "bidirectional"))
    )
    (net (code "51") (name "PA9{slash}INVH{slash}PH_MAG") (class "Default")
      (node (ref "DRIVER1") (pin "INVH") (pinfunction "INVH_INVH") (pintype "bidirectional"))
      (node (ref "R26") (pin "2") (pinfunction "2_2") (pintype "passive"))
      (node (ref "U6") (pin "19") (pinfunction "PA9_19") (pintype "bidirectional"))
    )
    (net (code "52") (name "PA10{slash}INWH") (class "Default")
      (node (ref "DRIVER1") (pin "INWH") (pinfunction "INWH_INWH") (pintype "bidirectional"))
      (node (ref "U6") (pin "20") (pinfunction "PA10_20") (pintype "bidirectional"))
    )
    (net (code "53") (name "PA15{slash}SPI1_NSS") (class "Default")
      (node (ref "U1") (pin "CSN") (pinfunction "CSN_CSN") (pintype "bidirectional"))
      (node (ref "U6") (pin "25") (pinfunction "PA15_25") (pintype "bidirectional"))
    )
    (net (code "54") (name "PB0{slash}INVL") (class "Default")
      (node (ref "DRIVER1") (pin "INVL") (pinfunction "INVL_INVL") (pintype "bidirectional"))
      (node (ref "U6") (pin "14") (pinfunction "PB0_14") (pintype "bidirectional"))
    )
    (net (code "55") (name "PB1{slash}INWL") (class "Default")
      (node (ref "DRIVER1") (pin "INWL") (pinfunction "INWL_INWL") (pintype "bidirectional"))
      (node (ref "U6") (pin "15") (pinfunction "PB1_15") (pintype "bidirectional"))
    )
    (net (code "56") (name "PB3{slash}EN_MAG") (class "Default")
      (node (ref "R_EN1") (pin "2") (pinfunction "2_2") (pintype "passive"))
      (node (ref "U6") (pin "26") (pinfunction "PB3_26") (pintype "bidirectional"))
    )
    (net (code "57") (name "PB4{slash}SPI1_MISO") (class "Default")
      (node (ref "U1") (pin "MISO") (pinfunction "MISO_MISO") (pintype "bidirectional"))
      (node (ref "U6") (pin "27") (pinfunction "PB4_27") (pintype "bidirectional"))
    )
    (net (code "58") (name "PB5") (class "Default")
      (node (ref "U6") (pin "28") (pinfunction "PB5_28") (pintype "bidirectional"))
    )
    (net (code "59") (name "PB6{slash}EN_BLDC") (class "Default")
      (node (ref "R_EN") (pin "2") (pinfunction "2_2") (pintype "passive"))
      (node (ref "U6") (pin "29") (pinfunction "PB6_29") (pintype "bidirectional"))
    )
    (net (code "60") (name "PB7") (class "Default")
      (node (ref "U6") (pin "30") (pinfunction "PB7_30") (pintype "bidirectional"))
    )
    (net (code "61") (name "STBY{slash}RESET_BLDC") (class "Default")
      (node (ref "C_STBY") (pin "1") (pinfunction "1_1") (pintype "passive"))
      (node (ref "DRIVER1") (pin "STBY/RESET") (pinfunction "STBY/RESET_STBY/RESET") (pintype "bidirectional"))
      (node (ref "R_STBY") (pin "1") (pinfunction "1_1") (pintype "passive"))
    )
    (net (code "62") (name "STBY{slash}RESET_MAG") (class "Default")
      (node (ref "C_STBY1") (pin "1") (pinfunction "1_1") (pintype "passive"))
      (node (ref "DRIVER2") (pin "14") (pinfunction "STBY/RESET_14") (pintype "bidirectional"))
      (node (ref "R_STBY1") (pin "1") (pinfunction "1_1") (pintype "passive"))
    )
    (net (code "63") (name "SWCLK") (class "Default")
      (node (ref "J1") (pin "4") (pinfunction "SWDCLK/TCK_4") (pintype "bidirectional"))
      (node (ref "U6") (pin "24") (pinfunction "PA14-SWCLK_24") (pintype "bidirectional"))
    )
    (net (code "64") (name "SWDIO") (class "Default")
      (node (ref "J1") (pin "2") (pinfunction "SWDIO/TMS_2") (pintype "bidirectional"))
      (node (ref "U6") (pin "23") (pinfunction "PA13-SWDIO_23") (pintype "bidirectional"))
    )
    (net (code "65") (name "V_BATT") (class "Default")
      (node (ref "C20") (pin "1") (pinfunction "1_1") (pintype "passive"))
      (node (ref "C23") (pin "1") (pinfunction "1_1") (pintype "passive"))
      (node (ref "JP1") (pin "3") (pinfunction "3_3") (pintype "passive"))
      (node (ref "R1") (pin "2") (pinfunction "2_2") (pintype "passive"))
      (node (ref "R12") (pin "2") (pinfunction "2_2") (pintype "passive"))
      (node (ref "R13") (pin "2") (pinfunction "2_2") (pintype "passive"))
      (node (ref "R20") (pin "2") (pinfunction "2_2") (pintype "passive"))
      (node (ref "U3") (pin "1") (pinfunction "VIN_1") (pintype "bidirectional"))
    )
    (net (code "66") (name "unconnected-(J1-NC{slash}TDI-Pad8)") (class "Default")
      (node (ref "J1") (pin "8") (pinfunction "NC/TDI_8") (pintype "bidirectional"))
    )
    (net (code "67") (name "unconnected-(J1-SWO{slash}TDO-Pad6)") (class "Default")
      (node (ref "J1") (pin "6") (pinfunction "SWO/TDO_6") (pintype "bidirectional"))
    )
    (net (code "68") (name "unconnected-(J5-CTS-PadP$5)") (class "Default")
      (node (ref "J5") (pin "P$5") (pinfunction "CTS_P$5") (pintype "passive"))
    )
    (net (code "69") (name "unconnected-(J5-DTR-PadP$1)") (class "Default")
      (node (ref "J5") (pin "P$1") (pinfunction "DTR_P$1") (pintype "passive"))
    )
    (net (code "70") (name "unconnected-(J5-VCC-PadP$4)") (class "Default")
      (node (ref "J5") (pin "P$4") (pinfunction "VCC_P$4") (pintype "passive"))
    )
    (net (code "71") (name "unconnected-(JP9-Pad2)") (class "Default")
      (node (ref "JP9") (pin "2") (pinfunction "2_2") (pintype "passive"))
    )
    (net (code "72") (name "unconnected-(U1-PadA)") (class "Default")
      (node (ref "U1") (pin "A") (pinfunction "A_A") (pintype "bidirectional"))
    )
    (net (code "73") (name "unconnected-(U1-PadB)") (class "Default")
      (node (ref "U1") (pin "B") (pinfunction "B_B") (pintype "bidirectional"))
    )
    (net (code "74") (name "unconnected-(U1-PadI{slash}PWM)") (class "Default")
      (node (ref "U1") (pin "I/PWM") (pinfunction "I/PWM_I/PWM") (pintype "bidirectional"))
    )
    (net (code "75") (name "unconnected-(U1-PadTEST)") (class "Default")
      (node (ref "U1") (pin "TEST") (pinfunction "TEST_TEST") (pintype "bidirectional"))
    )
    (net (code "76") (name "unconnected-(U1-PadU)") (class "Default")
      (node (ref "U1") (pin "U") (pinfunction "U_U") (pintype "bidirectional"))
    )
    (net (code "77") (name "unconnected-(U1-PadV)") (class "Default")
      (node (ref "U1") (pin "V") (pinfunction "V_V") (pintype "bidirectional"))
    )
    (net (code "78") (name "unconnected-(U1-PadW{slash}PWM)") (class "Default")
      (node (ref "U1") (pin "W/PWM") (pinfunction "W/PWM_W/PWM") (pintype "bidirectional"))
    )
  )
)
